# Management.net
KiCad netlist of a schematic drawn in Altium Designer
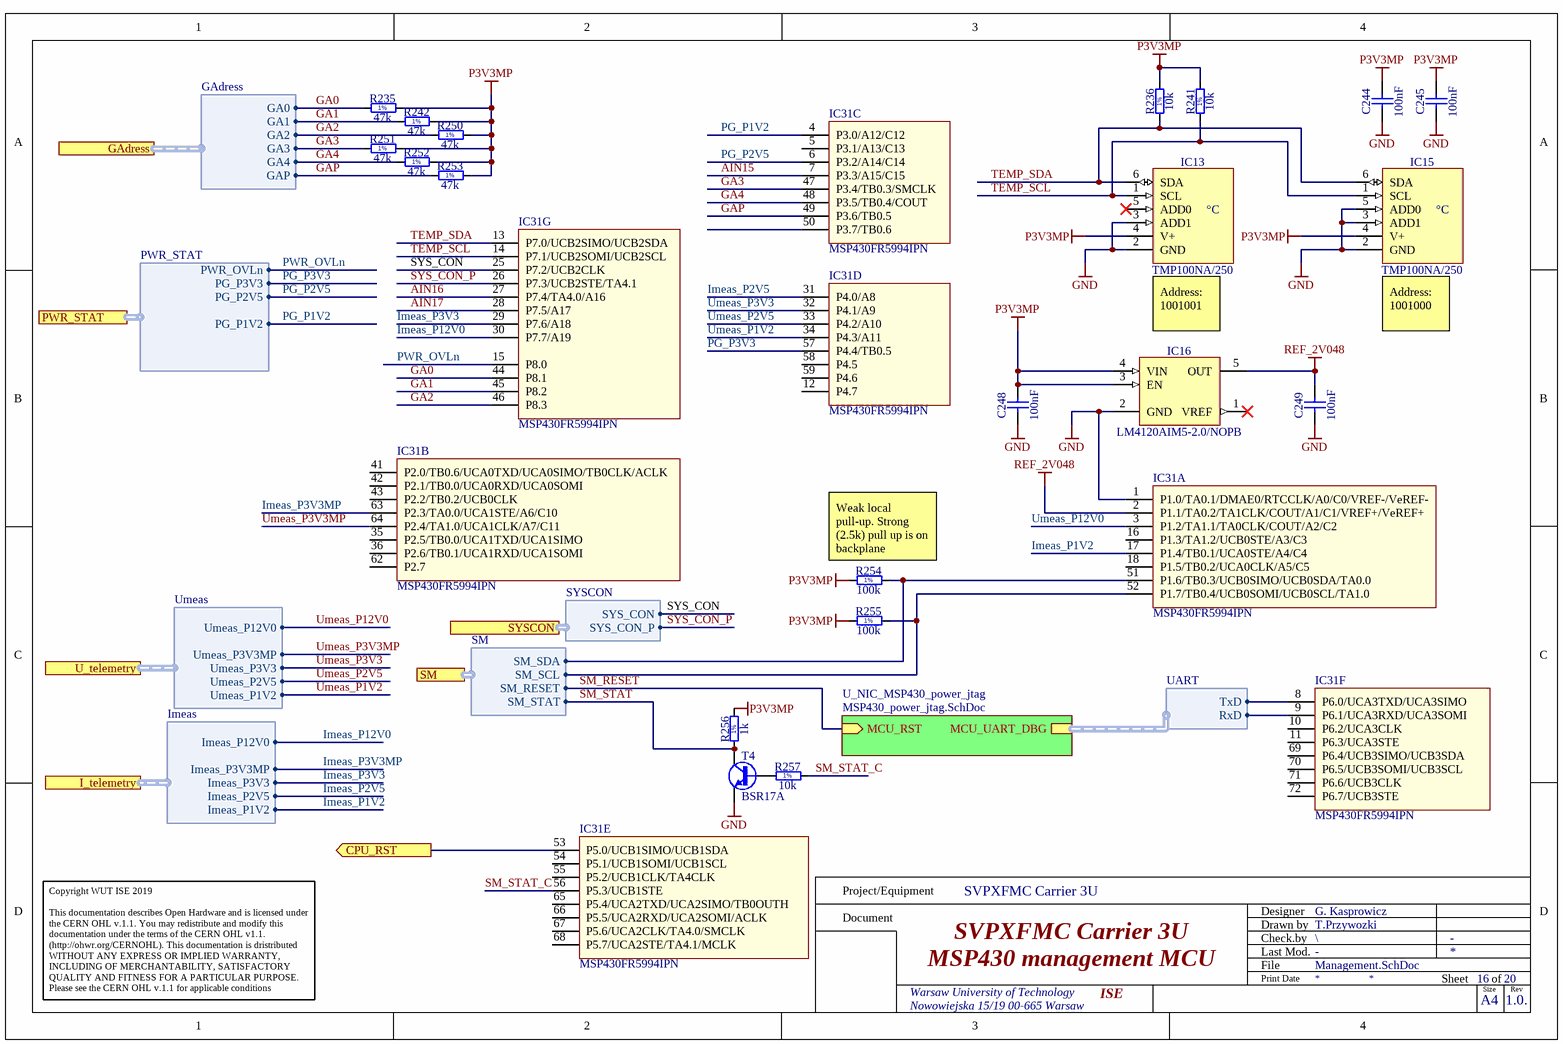
[diagram p0: Management.SchDoc]

(export (version "E")
  (design (tool "Eeschema 10.0.6"))
  (components
    (comp (ref "C244")
      (value "100nF")
      (footprint "CAPC1005X55N")
      (description "Non-polarised capacitor")
      (fields
        (field (name "PART NUMBER") "CC0402_100NF_25V_10%_X7R_YUDEN_TMK105B7104KVHF")
        (field (name "VOLTAGE") "25V")
        (field (name "AUTHOR") "CERN DEM JLC")
      )
      (libsource (lib "Capacitors") (part "Capacitor - non polarized"))
    )
    (comp (ref "C245")
      (value "100nF")
      (footprint "CAPC1005X55N")
      (description "Non-polarised capacitor")
      (fields
        (field (name "PART NUMBER") "CC0402_100NF_25V_10%_X7R_YUDEN_TMK105B7104KVHF")
        (field (name "VOLTAGE") "25V")
        (field (name "AUTHOR") "CERN DEM JLC")
      )
      (libsource (lib "Capacitors") (part "Capacitor - non polarized"))
    )
    (comp (ref "C248")
      (value "100nF")
      (footprint "CAPC1005X55N")
      (description "Non-polarised capacitor")
      (fields
        (field (name "PART NUMBER") "CC0402_100NF_25V_10%_X7R_YUDEN_TMK105B7104KVHF")
        (field (name "VOLTAGE") "25V")
        (field (name "AUTHOR") "CERN DEM JLC")
      )
      (libsource (lib "Capacitors") (part "Capacitor - non polarized"))
    )
    (comp (ref "C249")
      (value "100nF")
      (footprint "CAPC1005X55N")
      (description "Non-polarised capacitor")
      (fields
        (field (name "PART NUMBER") "CC0402_100NF_25V_10%_X7R_YUDEN_TMK105B7104KVHF")
        (field (name "VOLTAGE") "25V")
        (field (name "AUTHOR") "CERN DEM JLC")
      )
      (libsource (lib "Capacitors") (part "Capacitor - non polarized"))
    )
    (comp (ref "IC13")
      (value "TMP100NA/250")
      (footprint "SOT95P280X145-6N")
      (description "Digital Temperature Sensor with I2C Interface")
      (fields (field (name "MANUFACTURER") "TEXAS INSTRUMENTS") (field (name "AUTHOR") "CERN DEM JLC"))
      (libsource (lib "ICs And Semiconductors") (part "TMP100"))
    )
    (comp (ref "IC15")
      (value "TMP100NA/250")
      (footprint "SOT95P280X145-6N")
      (description "Digital Temperature Sensor with I2C Interface")
      (fields (field (name "MANUFACTURER") "TEXAS INSTRUMENTS") (field (name "AUTHOR") "CERN DEM JLC"))
      (libsource (lib "ICs And Semiconductors") (part "TMP100"))
    )
    (comp (ref "IC16")
      (value "LM4120AIM5-2.0/NOPB")
      (footprint "SOT95P280X145-5N")
      (description "Precision Micropower Low Dropout Voltage Reference")
      (fields (field (name "MANUFACTURER") "TEXAS INSTRUMENTS") (field (name "AUTHOR") "CERN DEM JMW"))
      (libsource (lib "ICs And Semiconductors") (part "LM4120"))
    )
    (comp (ref "IC31")
      (value "MSP430FR5994IPN")
      (footprint "PQFP50P1400X1400-80N")
      (fields (field (name "MANUFACTURER") "TI"))
      (libsource (lib "ICs_And_Semiconductors") (part "MSP430FR5994IPN"))
    )
    (comp (ref "R235")
      (value "47k")
      (footprint "RESC1005X40N")
      (description "Resistor - 1%")
      (fields
        (field (name "PART NUMBER") "R0402_47K_1%_0.0625W_100PPM")
        (field (name "POWER") "0.0625W")
        (field (name "AUTHOR") "CERN DEM JLC")
      )
      (libsource (lib "Resistors") (part "Resistor - 1%"))
    )
    (comp (ref "R236")
      (value "10k")
      (footprint "RESC1005X40N")
      (description "Resistor - 1%")
      (fields
        (field (name "PART NUMBER") "R0402_10K_1%_0.0625W_100PPM")
        (field (name "POWER") "0.0625W")
        (field (name "AUTHOR") "CERN DEM JLC")
      )
      (libsource (lib "Resistors") (part "Resistor - 1%"))
    )
    (comp (ref "R241")
      (value "10k")
      (footprint "RESC1005X40N")
      (description "Resistor - 1%")
      (fields
        (field (name "PART NUMBER") "R0402_10K_1%_0.0625W_100PPM")
        (field (name "POWER") "0.0625W")
        (field (name "AUTHOR") "CERN DEM JLC")
      )
      (libsource (lib "Resistors") (part "Resistor - 1%"))
    )
    (comp (ref "R242")
      (value "47k")
      (footprint "RESC1005X40N")
      (description "Resistor - 1%")
      (fields
        (field (name "PART NUMBER") "R0402_47K_1%_0.0625W_100PPM")
        (field (name "POWER") "0.0625W")
        (field (name "AUTHOR") "CERN DEM JLC")
      )
      (libsource (lib "Resistors") (part "Resistor - 1%"))
    )
    (comp (ref "R250")
      (value "47k")
      (footprint "RESC1005X40N")
      (description "Resistor - 1%")
      (fields
        (field (name "PART NUMBER") "R0402_47K_1%_0.0625W_100PPM")
        (field (name "POWER") "0.0625W")
        (field (name "AUTHOR") "CERN DEM JLC")
      )
      (libsource (lib "Resistors") (part "Resistor - 1%"))
    )
    (comp (ref "R251")
      (value "47k")
      (footprint "RESC1005X40N")
      (description "Resistor - 1%")
      (fields
        (field (name "PART NUMBER") "R0402_47K_1%_0.0625W_100PPM")
        (field (name "POWER") "0.0625W")
        (field (name "AUTHOR") "CERN DEM JLC")
      )
      (libsource (lib "Resistors") (part "Resistor - 1%"))
    )
    (comp (ref "R252")
      (value "47k")
      (footprint "RESC1005X40N")
      (description "Resistor - 1%")
      (fields
        (field (name "PART NUMBER") "R0402_47K_1%_0.0625W_100PPM")
        (field (name "POWER") "0.0625W")
        (field (name "AUTHOR") "CERN DEM JLC")
      )
      (libsource (lib "Resistors") (part "Resistor - 1%"))
    )
    (comp (ref "R253")
      (value "47k")
      (footprint "RESC1005X40N")
      (description "Resistor - 1%")
      (fields
        (field (name "PART NUMBER") "R0402_47K_1%_0.0625W_100PPM")
        (field (name "POWER") "0.0625W")
        (field (name "AUTHOR") "CERN DEM JLC")
      )
      (libsource (lib "Resistors") (part "Resistor - 1%"))
    )
    (comp (ref "R254")
      (value "100k")
      (footprint "RESC1005X40N")
      (description "Resistor - 1%")
      (fields
        (field (name "PART NUMBER") "R0402_100K_1%_0.0625W_100PPM")
        (field (name "POWER") "0.0625W")
        (field (name "AUTHOR") "CERN DEM JLC")
      )
      (libsource (lib "Resistors") (part "Resistor - 1%"))
    )
    (comp (ref "R255")
      (value "100k")
      (footprint "RESC1005X40N")
      (description "Resistor - 1%")
      (fields
        (field (name "PART NUMBER") "R0402_100K_1%_0.0625W_100PPM")
        (field (name "POWER") "0.0625W")
        (field (name "AUTHOR") "CERN DEM JLC")
      )
      (libsource (lib "Resistors") (part "Resistor - 1%"))
    )
    (comp (ref "R256")
      (value "1k")
      (footprint "RESC1005X40N")
      (description "Resistor - 1%")
      (fields
        (field (name "PART NUMBER") "R0402_1K_1%_0.0625W_100PPM")
        (field (name "POWER") "0.0625W")
        (field (name "AUTHOR") "CERN DEM JLC")
      )
      (libsource (lib "Resistors") (part "Resistor - 1%"))
    )
    (comp (ref "R257")
      (value "10k")
      (footprint "RESC1005X40N")
      (description "Resistor - 1%")
      (fields
        (field (name "PART NUMBER") "R0402_10K_1%_0.0625W_100PPM")
        (field (name "POWER") "0.0625W")
        (field (name "AUTHOR") "CERN DEM JLC")
      )
      (libsource (lib "Resistors") (part "Resistor - 1%"))
    )
    (comp (ref "T4")
      (value "BSR17A")
      (footprint "SOT95P240X110-3N")
      (description "NPN Transistor")
      (fields (field (name "MANUFACTURER") "FAIRCHILD SEMICONDUCTOR") (field (name "AUTHOR") "CERN DEM JLC"))
      (libsource (lib "ICs And Semiconductors") (part "NPN B1 E2 C3"))
    )
  )
  (nets
    (net (code "8") (name "/AIN15") (class "Default")
      (node (ref "IC31") (pin "7") (pinfunction "P3.3/A15/C15_7") (pintype "passive"))
    )
    (net (code "9") (name "/AIN16") (class "Default")
      (node (ref "IC31") (pin "27") (pinfunction "P7.4/TA4.0/A16_27") (pintype "passive"))
    )
    (net (code "10") (name "/AIN17") (class "Default")
      (node (ref "IC31") (pin "28") (pinfunction "P7.5/A17_28") (pintype "passive"))
    )
    (net (code "11") (name "/CPU_RST") (class "Default")
      (node (ref "IC31") (pin "53") (pinfunction "P5.0/UCB1SIMO/UCB1SDA_53") (pintype "passive"))
    )
    (net (code "12") (name "/GA0") (class "Default")
      (node (ref "IC31") (pin "44") (pinfunction "P8.1_44") (pintype "passive"))
      (node (ref "R235") (pin "1") (pinfunction "1_1") (pintype "passive"))
    )
    (net (code "13") (name "/GA1") (class "Default")
      (node (ref "IC31") (pin "45") (pinfunction "P8.2_45") (pintype "passive"))
      (node (ref "R242") (pin "1") (pinfunction "1_1") (pintype "passive"))
    )
    (net (code "14") (name "/GA2") (class "Default")
      (node (ref "IC31") (pin "46") (pinfunction "P8.3_46") (pintype "passive"))
      (node (ref "R250") (pin "1") (pinfunction "1_1") (pintype "passive"))
    )
    (net (code "15") (name "/GA3") (class "Default")
      (node (ref "IC31") (pin "47") (pinfunction "P3.4/TB0.3/SMCLK_47") (pintype "passive"))
      (node (ref "R251") (pin "1") (pinfunction "1_1") (pintype "passive"))
    )
    (net (code "16") (name "/GA4") (class "Default")
      (node (ref "IC31") (pin "48") (pinfunction "P3.5/TB0.4/COUT_48") (pintype "passive"))
      (node (ref "R252") (pin "1") (pinfunction "1_1") (pintype "passive"))
    )
    (net (code "17") (name "/GAP") (class "Default")
      (node (ref "IC31") (pin "49") (pinfunction "P3.6/TB0.5_49") (pintype "passive"))
      (node (ref "R253") (pin "1") (pinfunction "1_1") (pintype "passive"))
    )
    (net (code "18") (name "/Imeas_P1V2") (class "Default")
      (node (ref "IC31") (pin "17") (pinfunction "P1.4/TB0.1/UCA0STE/A4/C4_17") (pintype "passive"))
    )
    (net (code "19") (name "/Imeas_P2V5") (class "Default")
      (node (ref "IC31") (pin "31") (pinfunction "P4.0/A8_31") (pintype "passive"))
    )
    (net (code "20") (name "/Imeas_P3V3") (class "Default")
      (node (ref "IC31") (pin "29") (pinfunction "P7.6/A18_29") (pintype "passive"))
    )
    (net (code "21") (name "/Imeas_P3V3MP") (class "Default")
      (node (ref "IC31") (pin "63") (pinfunction "P2.3/TA0.0/UCA1STE/A6/C10_63") (pintype "passive"))
    )
    (net (code "22") (name "/Imeas_P12V0") (class "Default")
      (node (ref "IC31") (pin "30") (pinfunction "P7.7/A19_30") (pintype "passive"))
    )
    (net (code "23") (name "/PG_P1V2") (class "Default")
      (node (ref "IC31") (pin "4") (pinfunction "P3.0/A12/C12_4") (pintype "passive"))
    )
    (net (code "24") (name "/PG_P2V5") (class "Default")
      (node (ref "IC31") (pin "6") (pinfunction "P3.2/A14/C14_6") (pintype "passive"))
    )
    (net (code "25") (name "/PG_P3V3") (class "Default")
      (node (ref "IC31") (pin "57") (pinfunction "P4.4/TB0.5_57") (pintype "passive"))
    )
    (net (code "26") (name "/PWR_OVLn") (class "Default")
      (node (ref "IC31") (pin "15") (pinfunction "P8.0_15") (pintype "passive"))
    )
    (net (code "27") (name "/RxD") (class "Default")
      (node (ref "IC31") (pin "9") (pinfunction "P6.1/UCA3RXD/UCA3SOMI_9") (pintype "passive"))
    )
    (net (code "29") (name "/SM_SCL") (class "Default")
      (node (ref "IC31") (pin "52") (pinfunction "P1.7/TB0.4/UCB0SOMI/UCB0SCL/TA1.0_52") (pintype "passive"))
      (node (ref "R255") (pin "2") (pinfunction "2_2") (pintype "passive"))
    )
    (net (code "30") (name "/SM_SDA") (class "Default")
      (node (ref "IC31") (pin "51") (pinfunction "P1.6/TB0.3/UCB0SIMO/UCB0SDA/TA0.0_51") (pintype "passive"))
      (node (ref "R254") (pin "2") (pinfunction "2_2") (pintype "passive"))
    )
    (net (code "31") (name "/SM_STAT") (class "Default")
      (node (ref "R256") (pin "1") (pinfunction "1_1") (pintype "passive"))
      (node (ref "T4") (pin "3") (pinfunction "C_3") (pintype "passive"))
    )
    (net (code "32") (name "/SM_STAT_C") (class "Default")
      (node (ref "IC31") (pin "56") (pinfunction "P5.3/UCB1STE_56") (pintype "passive"))
      (node (ref "R257") (pin "2") (pinfunction "2_2") (pintype "passive"))
    )
    (net (code "33") (name "/SYS_CON") (class "Default")
      (node (ref "IC31") (pin "25") (pinfunction "P7.2/UCB2CLK_25") (pintype "passive"))
    )
    (net (code "34") (name "/SYS_CON_P") (class "Default")
      (node (ref "IC31") (pin "26") (pinfunction "P7.3/UCB2STE/TA4.1_26") (pintype "passive"))
    )
    (net (code "35") (name "/TEMP_SCL") (class "Default")
      (node (ref "IC13") (pin "1") (pinfunction "SCL_1") (pintype "input"))
      (node (ref "IC15") (pin "1") (pinfunction "SCL_1") (pintype "input"))
      (node (ref "IC31") (pin "14") (pinfunction "P7.1/UCB2SOMI/UCB2SCL_14") (pintype "passive"))
      (node (ref "R241") (pin "1") (pinfunction "1_1") (pintype "passive"))
    )
    (net (code "36") (name "/TEMP_SDA") (class "Default")
      (node (ref "IC13") (pin "6") (pinfunction "SDA_6") (pintype "bidirectional"))
      (node (ref "IC15") (pin "6") (pinfunction "SDA_6") (pintype "bidirectional"))
      (node (ref "IC31") (pin "13") (pinfunction "P7.0/UCB2SIMO/UCB2SDA_13") (pintype "passive"))
      (node (ref "R236") (pin "1") (pinfunction "1_1") (pintype "passive"))
    )
    (net (code "37") (name "/TxD") (class "Default")
      (node (ref "IC31") (pin "8") (pinfunction "P6.0/UCA3TXD/UCA3SIMO_8") (pintype "passive"))
    )
    (net (code "38") (name "/Umeas_P1V2") (class "Default")
      (node (ref "IC31") (pin "34") (pinfunction "P4.3/A11_34") (pintype "passive"))
    )
    (net (code "39") (name "/Umeas_P2V5") (class "Default")
      (node (ref "IC31") (pin "33") (pinfunction "P4.2/A10_33") (pintype "passive"))
    )
    (net (code "40") (name "/Umeas_P3V3") (class "Default")
      (node (ref "IC31") (pin "32") (pinfunction "P4.1/A9_32") (pintype "passive"))
    )
    (net (code "41") (name "/Umeas_P3V3MP") (class "Default")
      (node (ref "IC31") (pin "64") (pinfunction "P2.4/TA1.0/UCA1CLK/A7/C11_64") (pintype "passive"))
    )
    (net (code "42") (name "/Umeas_P12V0") (class "Default")
      (node (ref "IC31") (pin "3") (pinfunction "P1.2/TA1.1/TA0CLK/COUT/A2/C2_3") (pintype "passive"))
    )
    (net (code "50") (name "GND") (class "Default")
      (node (ref "C244") (pin "1") (pinfunction "1_1") (pintype "passive"))
      (node (ref "C245") (pin "1") (pinfunction "1_1") (pintype "passive"))
      (node (ref "C248") (pin "1") (pinfunction "1_1") (pintype "passive"))
      (node (ref "C249") (pin "1") (pinfunction "1_1") (pintype "passive"))
      (node (ref "IC13") (pin "2") (pinfunction "GND_2") (pintype "power_in"))
      (node (ref "IC13") (pin "3") (pinfunction "ADD1_3") (pintype "input"))
      (node (ref "IC15") (pin "2") (pinfunction "GND_2") (pintype "power_in"))
      (node (ref "IC15") (pin "3") (pinfunction "ADD1_3") (pintype "input"))
      (node (ref "IC15") (pin "5") (pinfunction "ADD0_5") (pintype "input"))
      (node (ref "IC16") (pin "2") (pinfunction "GND_2") (pintype "power_in"))
      (node (ref "IC31") (pin "1") (pinfunction "P1.0/TA0.1/DMAE0/RTCCLK/A0/C0/VREF-/VeREF-_1") (pintype "passive"))
      (node (ref "T4") (pin "2") (pinfunction "E_2") (pintype "passive"))
    )
    (net (code "51") (name "Net-(T4-B)") (class "Default")
      (node (ref "R257") (pin "1") (pinfunction "1_1") (pintype "passive"))
      (node (ref "T4") (pin "1") (pinfunction "B_1") (pintype "passive"))
    )
    (net (code "52") (name "P3V3MP") (class "Default")
      (node (ref "C244") (pin "2") (pinfunction "2_2") (pintype "passive"))
      (node (ref "C245") (pin "2") (pinfunction "2_2") (pintype "passive"))
      (node (ref "C248") (pin "2") (pinfunction "2_2") (pintype "passive"))
      (node (ref "IC13") (pin "4") (pinfunction "V+_4") (pintype "power_in"))
      (node (ref "IC15") (pin "4") (pinfunction "V+_4") (pintype "power_in"))
      (node (ref "IC16") (pin "3") (pinfunction "EN_3") (pintype "input"))
      (node (ref "IC16") (pin "4") (pinfunction "VIN_4") (pintype "input"))
      (node (ref "R235") (pin "2") (pinfunction "2_2") (pintype "passive"))
      (node (ref "R236") (pin "2") (pinfunction "2_2") (pintype "passive"))
      (node (ref "R241") (pin "2") (pinfunction "2_2") (pintype "passive"))
      (node (ref "R242") (pin "2") (pinfunction "2_2") (pintype "passive"))
      (node (ref "R250") (pin "2") (pinfunction "2_2") (pintype "passive"))
      (node (ref "R251") (pin "2") (pinfunction "2_2") (pintype "passive"))
      (node (ref "R252") (pin "2") (pinfunction "2_2") (pintype "passive"))
      (node (ref "R253") (pin "2") (pinfunction "2_2") (pintype "passive"))
      (node (ref "R254") (pin "1") (pinfunction "1_1") (pintype "passive"))
      (node (ref "R255") (pin "1") (pinfunction "1_1") (pintype "passive"))
      (node (ref "R256") (pin "2") (pinfunction "2_2") (pintype "passive"))
    )
    (net (code "53") (name "REF_2V048") (class "Default")
      (node (ref "C249") (pin "2") (pinfunction "2_2") (pintype "passive"))
      (node (ref "IC16") (pin "5") (pinfunction "OUT_5") (pintype "power_in"))
      (node (ref "IC31") (pin "2") (pinfunction "P1.1/TA0.2/TA1CLK/COUT/A1/C1/VREF+/VeREF+_2") (pintype "passive"))
    )
    (net (code "54") (name "unconnected-(IC13-ADD0-Pad5)") (class "Default")
      (node (ref "IC13") (pin "5") (pinfunction "ADD0_5") (pintype "input+no_connect"))
    )
    (net (code "55") (name "unconnected-(IC16-VREF-Pad1)") (class "Default")
      (node (ref "IC16") (pin "1") (pinfunction "VREF_1") (pintype "output+no_connect"))
    )
    (net (code "56") (name "unconnected-(IC31A-P1.3{slash}TA1.2{slash}UCB0STE{slash}A3{slash}C3-Pad16)") (class "Default")
      (node (ref "IC31") (pin "16") (pinfunction "P1.3/TA1.2/UCB0STE/A3/C3_16") (pintype "passive"))
    )
    (net (code "57") (name "unconnected-(IC31A-P1.5{slash}TB0.2{slash}UCA0CLK{slash}A5{slash}C5-Pad18)") (class "Default")
      (node (ref "IC31") (pin "18") (pinfunction "P1.5/TB0.2/UCA0CLK/A5/C5_18") (pintype "passive"))
    )
    (net (code "58") (name "unconnected-(IC31B-P2.0{slash}TB0.6{slash}UCA0TXD{slash}UCA0SIMO{slash}TB0CLK{slash}ACLK-Pad41)") (class "Default")
      (node (ref "IC31") (pin "41") (pinfunction "P2.0/TB0.6/UCA0TXD/UCA0SIMO/TB0CLK/ACLK_41") (pintype "passive"))
    )
    (net (code "59") (name "unconnected-(IC31B-P2.1{slash}TB0.0{slash}UCA0RXD{slash}UCA0SOMI-Pad42)") (class "Default")
      (node (ref "IC31") (pin "42") (pinfunction "P2.1/TB0.0/UCA0RXD/UCA0SOMI_42") (pintype "passive"))
    )
    (net (code "60") (name "unconnected-(IC31B-P2.2{slash}TB0.2{slash}UCB0CLK-Pad43)") (class "Default")
      (node (ref "IC31") (pin "43") (pinfunction "P2.2/TB0.2/UCB0CLK_43") (pintype "passive"))
    )
    (net (code "61") (name "unconnected-(IC31B-P2.5{slash}TB0.0{slash}UCA1TXD{slash}UCA1SIMO-Pad35)") (class "Default")
      (node (ref "IC31") (pin "35") (pinfunction "P2.5/TB0.0/UCA1TXD/UCA1SIMO_35") (pintype "passive"))
    )
    (net (code "62") (name "unconnected-(IC31B-P2.6{slash}TB0.1{slash}UCA1RXD{slash}UCA1SOMI-Pad36)") (class "Default")
      (node (ref "IC31") (pin "36") (pinfunction "P2.6/TB0.1/UCA1RXD/UCA1SOMI_36") (pintype "passive"))
    )
    (net (code "63") (name "unconnected-(IC31B-P2.7-Pad62)") (class "Default")
      (node (ref "IC31") (pin "62") (pinfunction "P2.7_62") (pintype "passive"))
    )
    (net (code "64") (name "unconnected-(IC31C-P3.1{slash}A13{slash}C13-Pad5)") (class "Default")
      (node (ref "IC31") (pin "5") (pinfunction "P3.1/A13/C13_5") (pintype "passive"))
    )
    (net (code "65") (name "unconnected-(IC31C-P3.7{slash}TB0.6-Pad50)") (class "Default")
      (node (ref "IC31") (pin "50") (pinfunction "P3.7/TB0.6_50") (pintype "passive"))
    )
    (net (code "66") (name "unconnected-(IC31D-P4.5-Pad58)") (class "Default")
      (node (ref "IC31") (pin "58") (pinfunction "P4.5_58") (pintype "passive"))
    )
    (net (code "67") (name "unconnected-(IC31D-P4.6-Pad59)") (class "Default")
      (node (ref "IC31") (pin "59") (pinfunction "P4.6_59") (pintype "passive"))
    )
    (net (code "68") (name "unconnected-(IC31D-P4.7-Pad12)") (class "Default")
      (node (ref "IC31") (pin "12") (pinfunction "P4.7_12") (pintype "passive"))
    )
    (net (code "69") (name "unconnected-(IC31E-P5.1{slash}UCB1SOMI{slash}UCB1SCL-Pad54)") (class "Default")
      (node (ref "IC31") (pin "54") (pinfunction "P5.1/UCB1SOMI/UCB1SCL_54") (pintype "passive"))
    )
    (net (code "70") (name "unconnected-(IC31E-P5.2{slash}UCB1CLK{slash}TA4CLK-Pad55)") (class "Default")
      (node (ref "IC31") (pin "55") (pinfunction "P5.2/UCB1CLK/TA4CLK_55") (pintype "passive"))
    )
    (net (code "71") (name "unconnected-(IC31E-P5.4{slash}UCA2TXD{slash}UCA2SIMO{slash}TB0OUTH-Pad65)") (class "Default")
      (node (ref "IC31") (pin "65") (pinfunction "P5.4/UCA2TXD/UCA2SIMO/TB0OUTH_65") (pintype "passive"))
    )
    (net (code "72") (name "unconnected-(IC31E-P5.5{slash}UCA2RXD{slash}UCA2SOMI{slash}ACLK-Pad66)") (class "Default")
      (node (ref "IC31") (pin "66") (pinfunction "P5.5/UCA2RXD/UCA2SOMI/ACLK_66") (pintype "passive"))
    )
    (net (code "73") (name "unconnected-(IC31E-P5.6{slash}UCA2CLK{slash}TA4.0{slash}SMCLK-Pad67)") (class "Default")
      (node (ref "IC31") (pin "67") (pinfunction "P5.6/UCA2CLK/TA4.0/SMCLK_67") (pintype "passive"))
    )
    (net (code "74") (name "unconnected-(IC31E-P5.7{slash}UCA2STE{slash}TA4.1{slash}MCLK-Pad68)") (class "Default")
      (node (ref "IC31") (pin "68") (pinfunction "P5.7/UCA2STE/TA4.1/MCLK_68") (pintype "passive"))
    )
    (net (code "75") (name "unconnected-(IC31F-P6.2{slash}UCA3CLK-Pad10)") (class "Default")
      (node (ref "IC31") (pin "10") (pinfunction "P6.2/UCA3CLK_10") (pintype "passive"))
    )
    (net (code "76") (name "unconnected-(IC31F-P6.3{slash}UCA3STE-Pad11)") (class "Default")
      (node (ref "IC31") (pin "11") (pinfunction "P6.3/UCA3STE_11") (pintype "passive"))
    )
    (net (code "77") (name "unconnected-(IC31F-P6.4{slash}UCB3SIMO{slash}UCB3SDA-Pad69)") (class "Default")
      (node (ref "IC31") (pin "69") (pinfunction "P6.4/UCB3SIMO/UCB3SDA_69") (pintype "passive"))
    )
    (net (code "78") (name "unconnected-(IC31F-P6.5{slash}UCB3SOMI{slash}UCB3SCL-Pad70)") (class "Default")
      (node (ref "IC31") (pin "70") (pinfunction "P6.5/UCB3SOMI/UCB3SCL_70") (pintype "passive"))
    )
    (net (code "79") (name "unconnected-(IC31F-P6.6{slash}UCB3CLK-Pad71)") (class "Default")
      (node (ref "IC31") (pin "71") (pinfunction "P6.6/UCB3CLK_71") (pintype "passive"))
    )
    (net (code "80") (name "unconnected-(IC31F-P6.7{slash}UCB3STE-Pad72)") (class "Default")
      (node (ref "IC31") (pin "72") (pinfunction "P6.7/UCB3STE_72") (pintype "passive"))
    )
  )
)
